# obc-v2_RTC-WDOG.net
KiCad netlist of a schematic drawn in Altium Designer
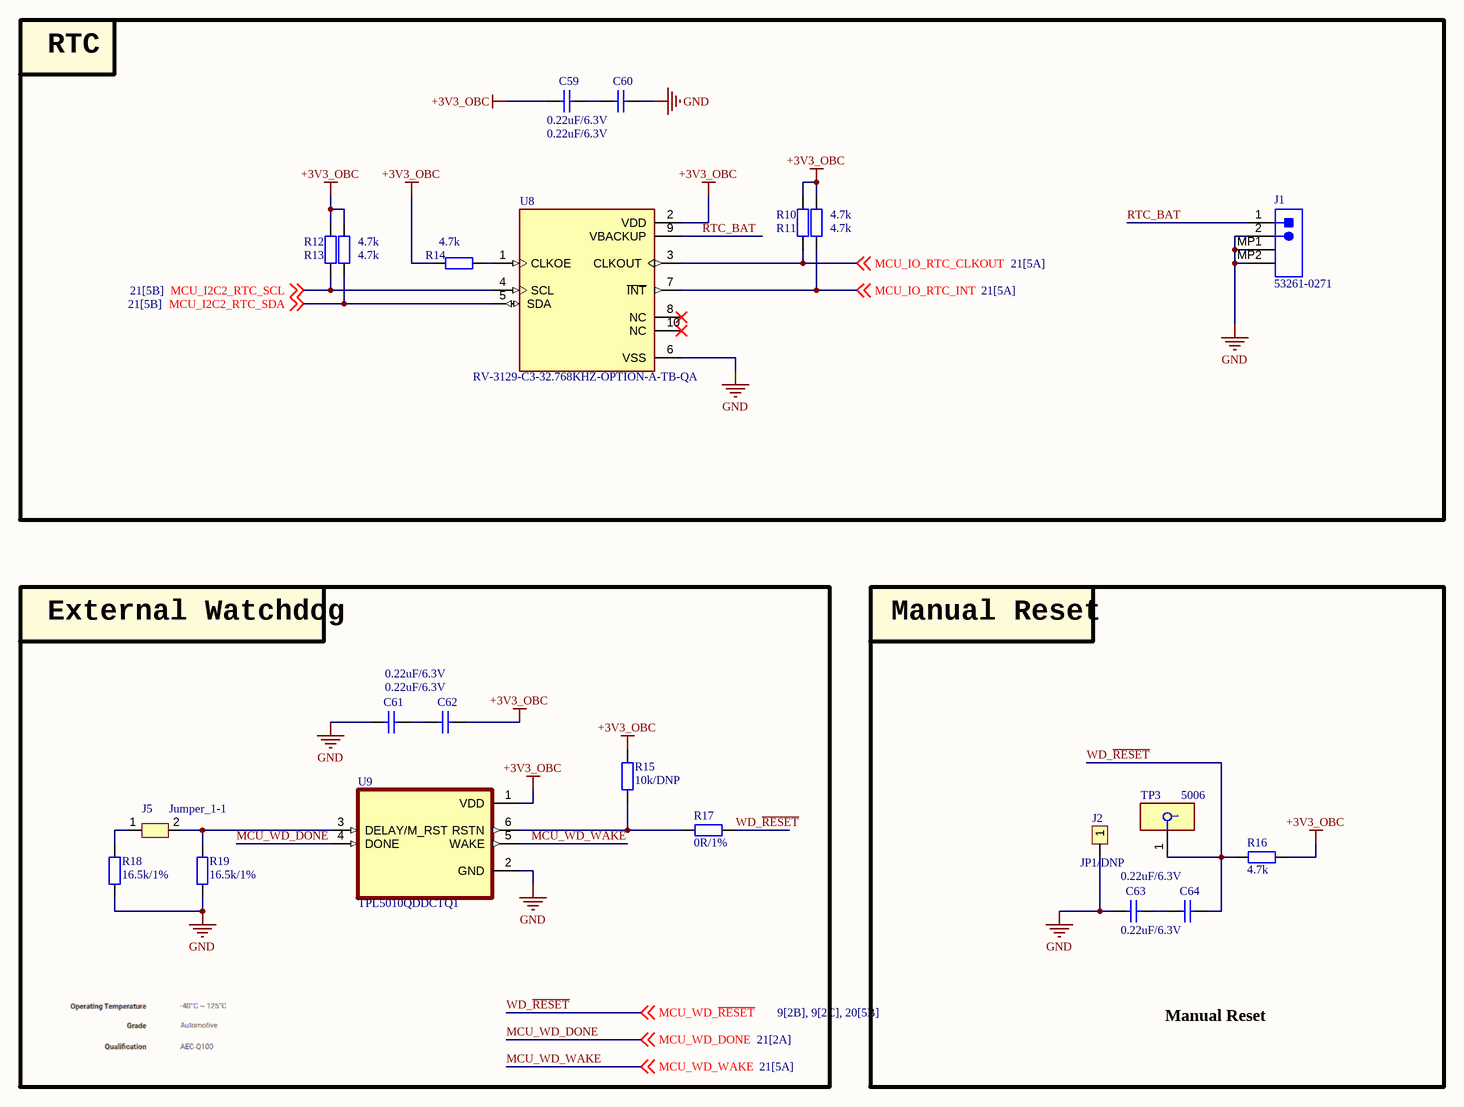
[diagram p0: obc-v2_RTC-WDOG.SchDoc]

(export (version "E")
  (design (tool "Eeschema 10.0.6"))
  (components
    (comp (ref "C59")
      (value "0.22uF/6.3V")
      (footprint "CAP_C_1005X60")
      (description "CAPC")
      (libsource (lib "Altium_Lib_by_KhueNguyenCreator") (part "Tu 0402 33nF 10V"))
    )
    (comp (ref "C60")
      (value "0.22uF/6.3V")
      (footprint "CAP_C_1005X60")
      (description "CAPC")
      (libsource (lib "Altium_Lib_by_KhueNguyenCreator") (part "Tu 0402 33nF 10V"))
    )
    (comp (ref "C61")
      (value "0.22uF/6.3V")
      (footprint "CAP_C_1005X60")
      (description "CAPC")
      (libsource (lib "Altium_Lib_by_KhueNguyenCreator") (part "Tu 0402 33nF 10V"))
    )
    (comp (ref "C62")
      (value "0.22uF/6.3V")
      (footprint "CAP_C_1005X60")
      (description "CAPC")
      (libsource (lib "Altium_Lib_by_KhueNguyenCreator") (part "Tu 0402 33nF 10V"))
    )
    (comp (ref "C63")
      (value "0.22uF/6.3V")
      (footprint "CAP_C_1005X60")
      (description "CAPC")
      (libsource (lib "Altium_Lib_by_KhueNguyenCreator") (part "Tu 0402 33nF 10V"))
    )
    (comp (ref "C64")
      (value "0.22uF/6.3V")
      (footprint "CAP_C_1005X60")
      (description "CAPC")
      (libsource (lib "Altium_Lib_by_KhueNguyenCreator") (part "Tu 0402 33nF 10V"))
    )
    (comp (ref "J1")
      (value "53261-0271")
      (footprint "MOLX-53261-0271_V")
      (description "PicoBlade(TM) Header, Right Angle, -40 to 85 degC, 2-Pin SMD, RoHS, Tape and Reel")
      (fields (field (name "MANUFACTURER") "Molex"))
      (libsource (lib "Altium Content Vault") (part "CN-1P-2M-R2"))
    )
    (comp (ref "J2")
      (value "JP1/DNP")
      (footprint "JP1-D1T")
      (description "WR-PHD 2.54 mm Angled Socket Header")
      (fields
        (field (name "MANUFACTURER") "Würth Elektronik eiSos GmbH")
        (field (name "PARTNO") "613002143121")
        (field (name "CREATED BY") "Karrer Zheng")
      )
      (libsource (lib "TechMT.VN_Lib_Project v2") (part "JP1"))
    )
    (comp (ref "J5")
      (value "Jumper_1-1")
      (footprint "Jumper_1-1")
      (libsource (lib "CAMERA_SchLib") (part "Jumper_1_1"))
    )
    (comp (ref "R10")
      (value "4.7k")
      (footprint "RES_C_1608X60")
      (description "RES")
      (libsource (lib "Altium_Lib_by_KhueNguyenCreator") (part "Tro 0603 1% 10k"))
    )
    (comp (ref "R11")
      (value "4.7k")
      (footprint "RES_C_1608X60")
      (description "RES")
      (libsource (lib "Altium_Lib_by_KhueNguyenCreator") (part "Tro 0603 1% 10k"))
    )
    (comp (ref "R12")
      (value "4.7k")
      (footprint "RES_C_1608X60")
      (description "RES")
      (libsource (lib "Altium_Lib_by_KhueNguyenCreator") (part "Tro 0603 1% 10k"))
    )
    (comp (ref "R13")
      (value "4.7k")
      (footprint "RES_C_1608X60")
      (description "RES")
      (libsource (lib "Altium_Lib_by_KhueNguyenCreator") (part "Tro 0603 1% 10k"))
    )
    (comp (ref "R14")
      (value "4.7k")
      (footprint "RES_C_1608X60")
      (description "RES")
      (libsource (lib "Altium_Lib_by_KhueNguyenCreator") (part "Tro 0603 1% 10k"))
    )
    (comp (ref "R15")
      (value "10k/DNP")
      (footprint "RES_C_1608X60")
      (description "RES SMD 10K OHM 1% 1/10W 0603, P/N: ERJ-3EKF1002V")
      (libsource (lib "Altium_Lib_by_KhueNguyenCreator") (part "Tro 0603 1% 10k"))
    )
    (comp (ref "R16")
      (value "4.7k")
      (footprint "RES_C_1608X60")
      (description "RES")
      (libsource (lib "Altium_Lib_by_KhueNguyenCreator") (part "Tro 0603 1% 10k"))
    )
    (comp (ref "R17")
      (value "0R/1%")
      (footprint "RES_C_1608X60")
      (description "RES")
      (libsource (lib "Altium_Lib_by_KhueNguyenCreator") (part "Tro 0603 1% 10k"))
    )
    (comp (ref "R18")
      (value "16.5k/1%")
      (footprint "RES_C_1608X60")
      (description "RES SMD 19.1K OHM 1% 1/10W 0603, P/N: ERJ-3EKF1912V")
      (libsource (lib "Altium_Lib_by_KhueNguyenCreator") (part "Tro 0603 1% 10k"))
    )
    (comp (ref "R19")
      (value "16.5k/1%")
      (footprint "RES_C_1608X60")
      (description "RES SMD 16.5K OHM 1% 1/10W 0603, P/N: ERJ-3EKF1652V")
      (libsource (lib "Altium_Lib_by_KhueNguyenCreator") (part "Tro 0603 1% 10k"))
    )
    (comp (ref "TP3")
      (value "5006")
      (footprint "FP-5006-MFG")
      (description "PC TEST POINT COMPACT BLACK")
      (libsource (lib "Altium Content Vault") (part "98815daf2f2c152b0c43f5ab9800df6"))
    )
    (comp (ref "U8")
      (value "RV-3129-C3-32.768KHZ-OPTION-A-TB-QA")
      (footprint "IC_RV-3129-C3_32.768KHZ_OPTION_A_TB_QA")
      (description "Real-Time Clock Module, Temperature compensated, in 2.5 x 3.7 mm package")
      (fields (field (name "MF") "Micro Crystal") (field (name "MP") "RV-3129-C3 32.768KHZ OPTION A TB QA"))
      (libsource (lib "RV-3129-C3_32.768KHZ_OPTION_A_TB_QA") (part "RV-3129-C3_32.768KHZ_OPTION_A_TB_QA"))
    )
    (comp (ref "U9")
      (value "TPL5010QDDCTQ1")
      (footprint "SOT95P280X110-6N")
      (libsource (lib "TPL5010QDDCTQ1") (part "TPL5010QDDCTQ1"))
    )
  )
  (nets
    (net (code "1") (name "+3V3_OBC") (class "Default")
      (node (ref "C59") (pin "2") (pinfunction "2_2") (pintype "passive"))
      (node (ref "C62") (pin "1") (pinfunction "1_1") (pintype "passive"))
      (node (ref "R10") (pin "2") (pinfunction "2_2") (pintype "passive"))
      (node (ref "R11") (pin "2") (pinfunction "2_2") (pintype "passive"))
      (node (ref "R12") (pin "2") (pinfunction "2_2") (pintype "passive"))
      (node (ref "R13") (pin "2") (pinfunction "2_2") (pintype "passive"))
      (node (ref "R14") (pin "2") (pinfunction "2_2") (pintype "passive"))
      (node (ref "R15") (pin "2") (pinfunction "2_2") (pintype "passive"))
      (node (ref "R16") (pin "2") (pinfunction "2_2") (pintype "passive"))
      (node (ref "U8") (pin "2") (pinfunction "VDD_2") (pintype "power_in"))
      (node (ref "U9") (pin "1") (pinfunction "VDD_1") (pintype "power_in"))
    )
    (net (code "2") (name "/RTC_BAT") (class "Default")
      (node (ref "J1") (pin "1") (pinfunction "1_1") (pintype "passive"))
      (node (ref "U8") (pin "9") (pinfunction "VBACKUP_9") (pintype "power_in"))
    )
    (net (code "3") (name "GND") (class "Default")
      (node (ref "C60") (pin "1") (pinfunction "1_1") (pintype "passive"))
      (node (ref "C61") (pin "2") (pinfunction "2_2") (pintype "passive"))
      (node (ref "C63") (pin "2") (pinfunction "2_2") (pintype "passive"))
      (node (ref "J1") (pin "2") (pinfunction "2_2") (pintype "passive"))
      (node (ref "J1") (pin "MP1") (pinfunction "MP1_MP1") (pintype "passive"))
      (node (ref "J1") (pin "MP2") (pinfunction "MP2_MP2") (pintype "passive"))
      (node (ref "J2") (pin "1") (pinfunction "1_1") (pintype "passive"))
      (node (ref "R18") (pin "1") (pinfunction "1_1") (pintype "passive"))
      (node (ref "R19") (pin "1") (pinfunction "1_1") (pintype "passive"))
      (node (ref "U8") (pin "6") (pinfunction "VSS_6") (pintype "power_in"))
      (node (ref "U9") (pin "2") (pinfunction "GND_2") (pintype "power_in"))
    )
    (net (code "4") (name "MCU_I2C2_RTC_SCL") (class "Default")
      (node (ref "R13") (pin "1") (pinfunction "1_1") (pintype "passive"))
      (node (ref "U8") (pin "4") (pinfunction "SCL_4") (pintype "input"))
    )
    (net (code "5") (name "MCU_I2C2_RTC_SDA") (class "Default")
      (node (ref "R12") (pin "1") (pinfunction "1_1") (pintype "passive"))
      (node (ref "U8") (pin "5") (pinfunction "SDA_5") (pintype "bidirectional"))
    )
    (net (code "6") (name "MCU_IO_RTC_CLKOUT") (class "Default")
      (node (ref "R11") (pin "1") (pinfunction "1_1") (pintype "passive"))
      (node (ref "U8") (pin "3") (pinfunction "CLKOUT_3") (pintype "output"))
    )
    (net (code "7") (name "MCU_IO_RTC_INT") (class "Default")
      (node (ref "R10") (pin "1") (pinfunction "1_1") (pintype "passive"))
      (node (ref "U8") (pin "7") (pinfunction "~{INT}_7") (pintype "output"))
    )
    (net (code "8") (name "MCU_WD_DONE") (class "Default")
      (node (ref "U9") (pin "4") (pinfunction "DONE_4") (pintype "input"))
    )
    (net (code "9") (name "MCU_WD_WAKE") (class "Default")
      (node (ref "U9") (pin "5") (pinfunction "WAKE_5") (pintype "output"))
    )
    (net (code "10") (name "MCU_WD_~{RESET}") (class "Default")
      (node (ref "C64") (pin "1") (pinfunction "1_1") (pintype "passive"))
      (node (ref "R16") (pin "1") (pinfunction "1_1") (pintype "passive"))
      (node (ref "R17") (pin "1") (pinfunction "1_1") (pintype "passive"))
      (node (ref "TP3") (pin "1") (pinfunction "1_1") (pintype "passive"))
    )
    (net (code "11") (name "Net-(C59-Pad1)") (class "Default")
      (node (ref "C59") (pin "1") (pinfunction "1_1") (pintype "passive"))
      (node (ref "C60") (pin "2") (pinfunction "2_2") (pintype "passive"))
    )
    (net (code "12") (name "Net-(C61-Pad1)") (class "Default")
      (node (ref "C61") (pin "1") (pinfunction "1_1") (pintype "passive"))
      (node (ref "C62") (pin "2") (pinfunction "2_2") (pintype "passive"))
    )
    (net (code "13") (name "Net-(C63-Pad1)") (class "Default")
      (node (ref "C63") (pin "1") (pinfunction "1_1") (pintype "passive"))
      (node (ref "C64") (pin "2") (pinfunction "2_2") (pintype "passive"))
    )
    (net (code "14") (name "Net-(J5-Pad1)") (class "Default")
      (node (ref "J5") (pin "1") (pintype "passive"))
      (node (ref "R18") (pin "2") (pinfunction "2_2") (pintype "passive"))
    )
    (net (code "15") (name "Net-(U8-CLKOE)") (class "Default")
      (node (ref "R14") (pin "1") (pinfunction "1_1") (pintype "passive"))
      (node (ref "U8") (pin "1") (pinfunction "CLKOE_1") (pintype "input"))
    )
    (net (code "16") (name "Net-(U9-DELAY{slash}M_RST)") (class "Default")
      (node (ref "J5") (pin "2") (pintype "passive"))
      (node (ref "R19") (pin "2") (pinfunction "2_2") (pintype "passive"))
      (node (ref "U9") (pin "3") (pinfunction "DELAY/M_RST_3") (pintype "input"))
    )
    (net (code "17") (name "Net-(U9-RSTN)") (class "Default")
      (node (ref "R15") (pin "1") (pinfunction "1_1") (pintype "passive"))
      (node (ref "R17") (pin "2") (pinfunction "2_2") (pintype "passive"))
      (node (ref "U9") (pin "6") (pinfunction "RSTN_6") (pintype "output"))
    )
    (net (code "18") (name "unconnected-(U8-NC-Pad8)") (class "Default")
      (node (ref "U8") (pin "8") (pinfunction "NC_8") (pintype "passive+no_connect"))
    )
    (net (code "19") (name "unconnected-(U8-NC-Pad10)") (class "Default")
      (node (ref "U8") (pin "10") (pinfunction "NC_10") (pintype "passive+no_connect"))
    )
  )
)
